# DC-DC_SY8120B1.net
KiCad netlist of a schematic drawn in Altium Designer
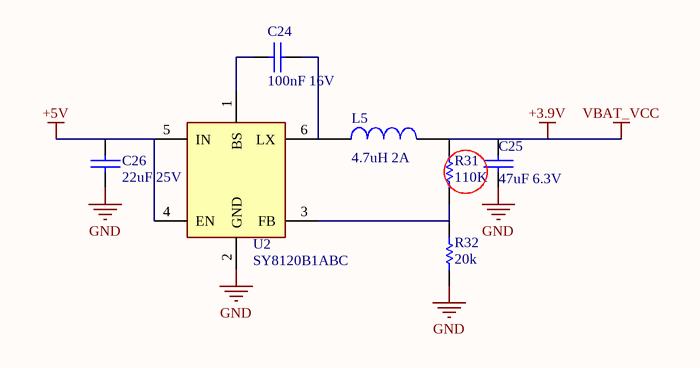
[diagram p0: DC-DC SY8120B1.SchDoc]

(export (version "E")
  (design (tool "Eeschema 10.0.6"))
  (components
    (comp (ref "C24") (value "100nF 16V") (footprint "电容:0402C") (libsource (lib "电容") (part "CAP-NP")))
    (comp (ref "C25") (value "47uF 6.3V") (footprint "电容:0805C") (libsource (lib "电容") (part "CAP-NP")))
    (comp (ref "C26")
      (value "22uF 25V")
      (footprint "电容:0805C")
      (description "22uF (226) ±20% 25V X5R")
      (libsource (lib "电容") (part "CAP-NP"))
    )
    (comp (ref "L5")
      (value "4.7uH 2A")
      (footprint "CD32")
      (description "INDUCTOR")
      (libsource (lib "电感") (part "INDUCTOR"))
    )
    (comp (ref "R31")
      (value "110K")
      (footprint "[01]PCB_ComputerVision2:0402R")
      (libsource (lib "电阻") (part "RES"))
    )
    (comp (ref "R32")
      (value "20k")
      (footprint "[01]PCB_ComputerVision2:0402R")
      (libsource (lib "电阻") (part "RES"))
    )
    (comp (ref "U2")
      (value "SY8120B1ABC")
      (footprint "SOT23-6")
      (fields (field (name "MANUFACTURER_PART_NUMBER") "SY8088AAC"))
      (libsource (lib "电源芯片") (part "SY8120B1ABC"))
    )
  )
  (nets
    (net (code "1") (name "+3.9V") (class "Default")
      (node (ref "C25") (pin "2") (pinfunction "2_2") (pintype "passive"))
      (node (ref "L5") (pin "2") (pinfunction "2_2") (pintype "passive"))
      (node (ref "R31") (pin "2") (pinfunction "2_2") (pintype "passive"))
    )
    (net (code "2") (name "+5V") (class "Default")
      (node (ref "C26") (pin "2") (pinfunction "2_2") (pintype "passive"))
      (node (ref "U2") (pin "4") (pinfunction "EN_4") (pintype "passive"))
      (node (ref "U2") (pin "5") (pinfunction "IN_5") (pintype "passive"))
    )
    (net (code "3") (name "GND") (class "Default")
      (node (ref "C25") (pin "1") (pinfunction "1_1") (pintype "passive"))
      (node (ref "C26") (pin "1") (pinfunction "1_1") (pintype "passive"))
      (node (ref "R32") (pin "1") (pinfunction "1_1") (pintype "passive"))
      (node (ref "U2") (pin "2") (pinfunction "GND_2") (pintype "passive"))
    )
    (net (code "4") (name "Net-(U2-BS)") (class "Default")
      (node (ref "C24") (pin "2") (pinfunction "2_2") (pintype "passive"))
      (node (ref "U2") (pin "1") (pinfunction "BS_1") (pintype "passive"))
    )
    (net (code "5") (name "Net-(U2-FB)") (class "Default")
      (node (ref "R31") (pin "1") (pinfunction "1_1") (pintype "passive"))
      (node (ref "R32") (pin "2") (pinfunction "2_2") (pintype "passive"))
      (node (ref "U2") (pin "3") (pinfunction "FB_3") (pintype "passive"))
    )
    (net (code "6") (name "Net-(U2-LX)") (class "Default")
      (node (ref "C24") (pin "1") (pinfunction "1_1") (pintype "passive"))
      (node (ref "L5") (pin "1") (pinfunction "1_1") (pintype "passive"))
      (node (ref "U2") (pin "6") (pinfunction "LX_6") (pintype "passive"))
    )
  )
)
